# CatPlay.net
KiCad netlist of a schematic drawn in EAGLE
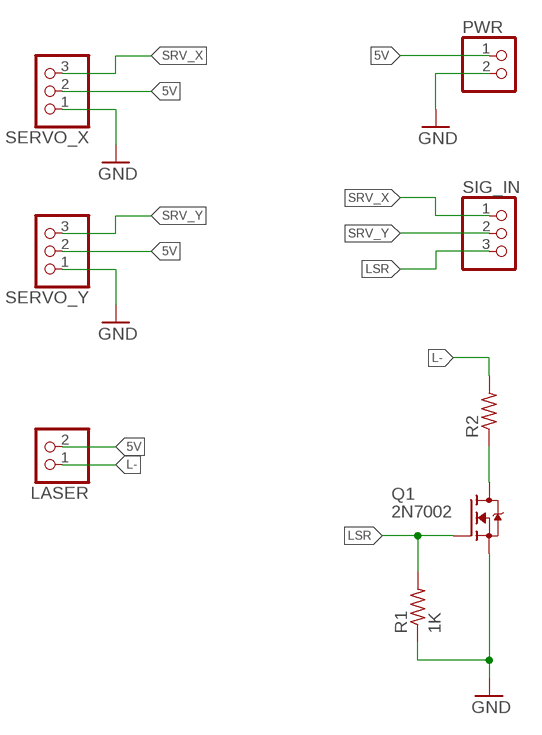
[diagram p0: schematic, sheet 1]

(export (version "E")
  (design (tool "Eeschema 10.0.6"))
  (components
    (comp (ref "LASER")
      (value "PINHD-1X2")
      (footprint "eagle-import:1X02")
      (libsource (lib "eagle-import") (part "PINHD-1X2"))
    )
    (comp (ref "PWR")
      (value "PINHD-1X2")
      (footprint "eagle-import:1X02")
      (libsource (lib "eagle-import") (part "PINHD-1X2"))
    )
    (comp (ref "Q1")
      (value "2N7002")
      (footprint "eagle-import:SOT-23")
      (libsource (lib "eagle-import") (part "2N7002"))
    )
    (comp (ref "R1")
      (value "1K")
      (footprint "eagle-import:R0603")
      (libsource (lib "eagle-import") (part "R-US_R0603"))
    )
    (comp (ref "R2")
      (value "R-US_R0603")
      (footprint "eagle-import:R0603")
      (libsource (lib "eagle-import") (part "R-US_R0603"))
    )
    (comp (ref "SERVO_X")
      (value "PINHD-1X3")
      (footprint "eagle-import:1X03")
      (libsource (lib "eagle-import") (part "PINHD-1X3"))
    )
    (comp (ref "SERVO_Y")
      (value "PINHD-1X3")
      (footprint "eagle-import:1X03")
      (libsource (lib "eagle-import") (part "PINHD-1X3"))
    )
    (comp (ref "SIG_IN")
      (value "PINHD-1X3")
      (footprint "eagle-import:1X03")
      (libsource (lib "eagle-import") (part "PINHD-1X3"))
    )
  )
  (nets
    (net (code "1") (name "5V") (class "Default")
      (node (ref "LASER") (pin "2") (pinfunction "2_2") (pintype "passive"))
      (node (ref "PWR") (pin "1") (pinfunction "1_1") (pintype "passive"))
      (node (ref "SERVO_X") (pin "2") (pinfunction "2_2") (pintype "passive"))
      (node (ref "SERVO_Y") (pin "2") (pinfunction "2_2") (pintype "passive"))
    )
    (net (code "2") (name "GND") (class "Default")
      (node (ref "PWR") (pin "2") (pinfunction "2_2") (pintype "passive"))
      (node (ref "Q1") (pin "2") (pinfunction "S_2") (pintype "passive"))
      (node (ref "R1") (pin "1") (pinfunction "1_1") (pintype "passive"))
      (node (ref "SERVO_X") (pin "1") (pinfunction "1_1") (pintype "passive"))
      (node (ref "SERVO_Y") (pin "1") (pinfunction "1_1") (pintype "passive"))
    )
    (net (code "3") (name "L-") (class "Default")
      (node (ref "LASER") (pin "1") (pinfunction "1_1") (pintype "passive"))
      (node (ref "R2") (pin "2") (pinfunction "2_2") (pintype "passive"))
    )
    (net (code "4") (name "LSR") (class "Default")
      (node (ref "Q1") (pin "1") (pinfunction "G_1") (pintype "passive"))
      (node (ref "R1") (pin "2") (pinfunction "2_2") (pintype "passive"))
      (node (ref "SIG_IN") (pin "3") (pinfunction "3_3") (pintype "passive"))
    )
    (net (code "5") (name "Net-(Q1-D)") (class "Default")
      (node (ref "Q1") (pin "3") (pinfunction "D_3") (pintype "passive"))
      (node (ref "R2") (pin "1") (pinfunction "1_1") (pintype "passive"))
    )
    (net (code "6") (name "SRV_X") (class "Default")
      (node (ref "SERVO_X") (pin "3") (pinfunction "3_3") (pintype "passive"))
      (node (ref "SIG_IN") (pin "1") (pinfunction "1_1") (pintype "passive"))
    )
    (net (code "7") (name "SRV_Y") (class "Default")
      (node (ref "SERVO_Y") (pin "3") (pinfunction "3_3") (pintype "passive"))
      (node (ref "SIG_IN") (pin "2") (pinfunction "2_2") (pintype "passive"))
    )
  )
)
